# Driver.net
KiCad netlist of a schematic drawn in Altium Designer
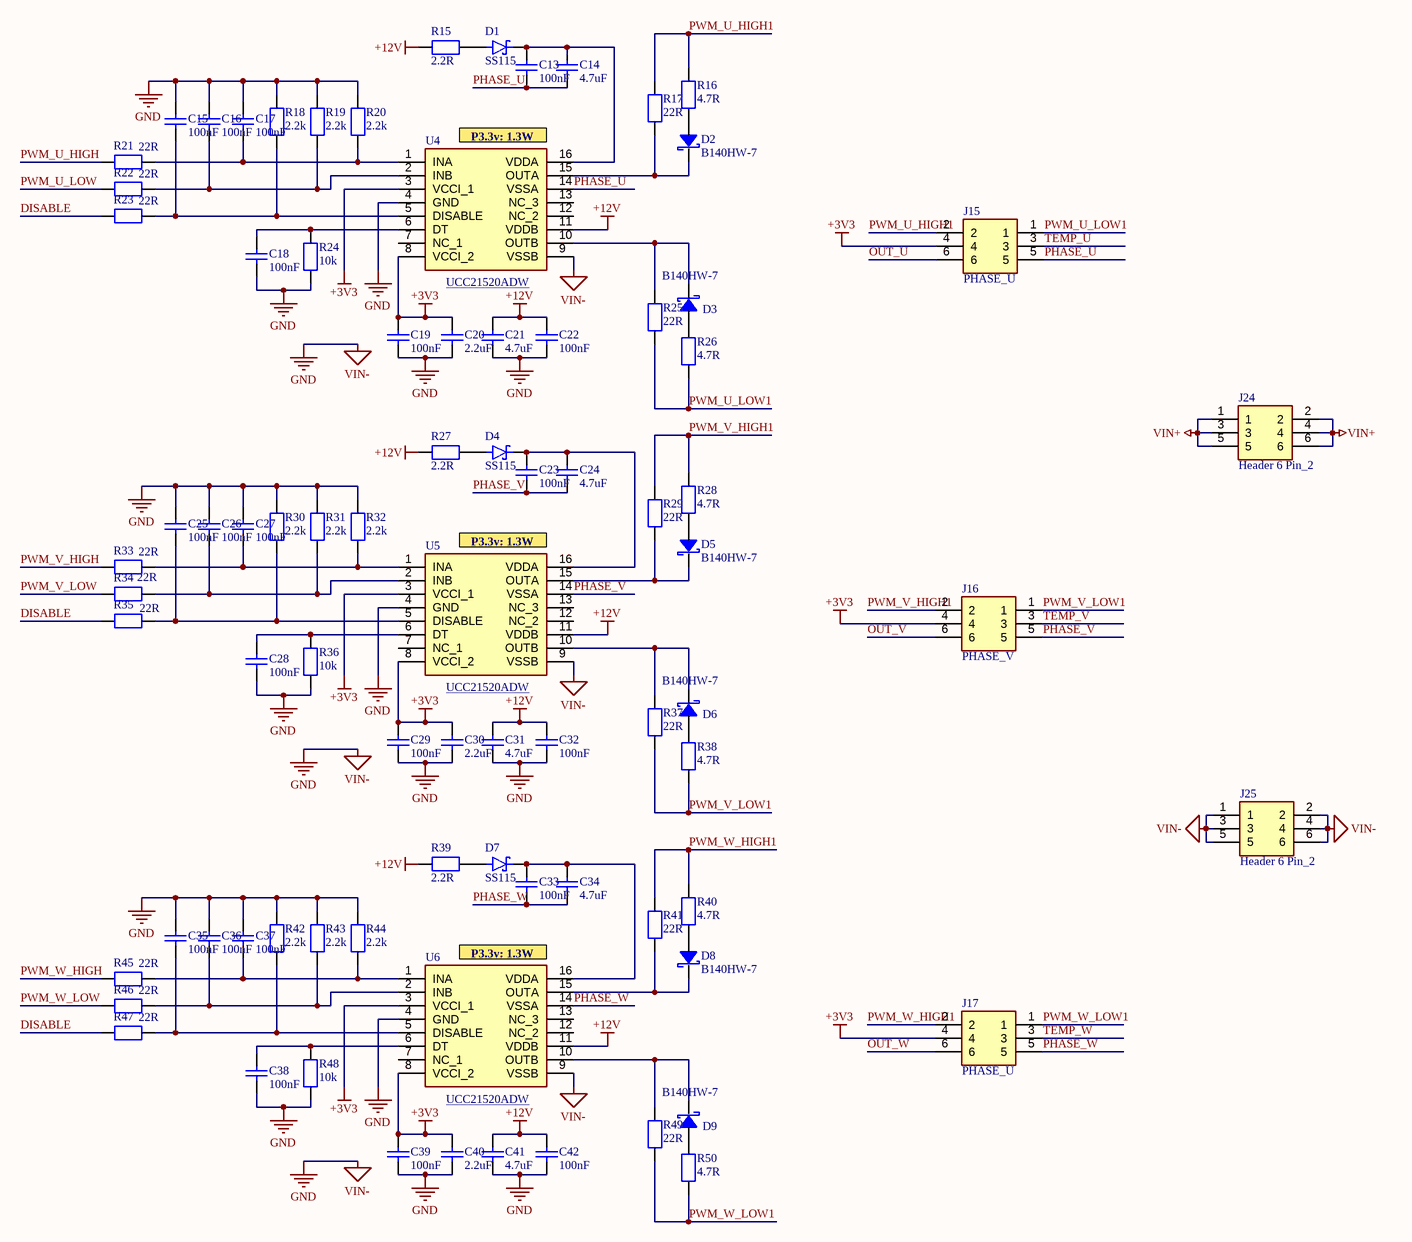
[diagram p0: Driver.SchDoc]

(export (version "E")
  (design (tool "Eeschema 10.0.6"))
  (components
    (comp (ref "C13")
      (value "100nF")
      (footprint "C0603")
      (description "100nF ± 10% 50V")
      (fields
        (field (name "MANUFACTURER") "Yageo")
        (field (name "MANUFACTURER PART NUMBER") "CS0603KRX7R9BB104")
      )
      (libsource (lib "VESC_MotorController") (part "100nF ± 10% 50V"))
    )
    (comp (ref "C14")
      (value "4.7uF")
      (footprint "C0603")
      (description "4.7uF ± 10% 50V")
      (fields
        (field (name "MANUFACTURER") "Yageo")
        (field (name "MANUFACTURER PART NUMBER") "GRM188R61H225ME11J")
      )
      (libsource (lib "VESC_MotorController") (part "4.7uF ± 10% 50V"))
    )
    (comp (ref "C15")
      (value "100nF")
      (footprint "C0603")
      (description "100nF ± 10% 50V")
      (fields
        (field (name "MANUFACTURER") "Yageo")
        (field (name "MANUFACTURER PART NUMBER") "CS0603KRX7R9BB104")
      )
      (libsource (lib "VESC_MotorController") (part "100nF ± 10% 50V"))
    )
    (comp (ref "C16")
      (value "100nF")
      (footprint "C0603")
      (description "100nF ± 10% 50V")
      (fields
        (field (name "MANUFACTURER") "Yageo")
        (field (name "MANUFACTURER PART NUMBER") "CS0603KRX7R9BB104")
      )
      (libsource (lib "VESC_MotorController") (part "100nF ± 10% 50V"))
    )
    (comp (ref "C17")
      (value "100nF")
      (footprint "C0603")
      (description "100nF ± 10% 50V")
      (fields
        (field (name "MANUFACTURER") "Yageo")
        (field (name "MANUFACTURER PART NUMBER") "CS0603KRX7R9BB104")
      )
      (libsource (lib "VESC_MotorController") (part "100nF ± 10% 50V"))
    )
    (comp (ref "C18")
      (value "100nF")
      (footprint "C0603")
      (description "100nF ± 10% 50V")
      (fields
        (field (name "MANUFACTURER") "Yageo")
        (field (name "MANUFACTURER PART NUMBER") "CS0603KRX7R9BB104")
      )
      (libsource (lib "VESC_MotorController") (part "100nF ± 10% 50V"))
    )
    (comp (ref "C19")
      (value "100nF")
      (footprint "C0603")
      (description "100nF ± 10% 50V")
      (fields
        (field (name "MANUFACTURER") "Yageo")
        (field (name "MANUFACTURER PART NUMBER") "CS0603KRX7R9BB104")
      )
      (libsource (lib "VESC_MotorController") (part "100nF ± 10% 50V"))
    )
    (comp (ref "C20")
      (value "2.2uF")
      (footprint "C0603")
      (description "2.2uF ± 10% 50V")
      (fields
        (field (name "MANUFACTURER") "Yageo")
        (field (name "MANUFACTURER PART NUMBER") "GRM188R61H225ME11J")
      )
      (libsource (lib "VESC_MotorController") (part "2.2uF ± 10% 50V"))
    )
    (comp (ref "C21")
      (value "4.7uF")
      (footprint "C0603")
      (description "4.7uF ± 10% 50V")
      (fields
        (field (name "MANUFACTURER") "Yageo")
        (field (name "MANUFACTURER PART NUMBER") "GRM188R61H225ME11J")
      )
      (libsource (lib "VESC_MotorController") (part "4.7uF ± 10% 50V"))
    )
    (comp (ref "C22")
      (value "100nF")
      (footprint "C0603")
      (description "100nF ± 10% 50V")
      (fields
        (field (name "MANUFACTURER") "Yageo")
        (field (name "MANUFACTURER PART NUMBER") "CS0603KRX7R9BB104")
      )
      (libsource (lib "VESC_MotorController") (part "100nF ± 10% 50V"))
    )
    (comp (ref "C23")
      (value "100nF")
      (footprint "C0603")
      (description "100nF ± 10% 50V")
      (fields
        (field (name "MANUFACTURER") "Yageo")
        (field (name "MANUFACTURER PART NUMBER") "CS0603KRX7R9BB104")
      )
      (libsource (lib "VESC_MotorController") (part "100nF ± 10% 50V"))
    )
    (comp (ref "C24")
      (value "4.7uF")
      (footprint "C0603")
      (description "4.7uF ± 10% 50V")
      (fields
        (field (name "MANUFACTURER") "Yageo")
        (field (name "MANUFACTURER PART NUMBER") "GRM188R61H225ME11J")
      )
      (libsource (lib "VESC_MotorController") (part "4.7uF ± 10% 50V"))
    )
    (comp (ref "C25")
      (value "100nF")
      (footprint "C0603")
      (description "100nF ± 10% 50V")
      (fields
        (field (name "MANUFACTURER") "Yageo")
        (field (name "MANUFACTURER PART NUMBER") "CS0603KRX7R9BB104")
      )
      (libsource (lib "VESC_MotorController") (part "100nF ± 10% 50V"))
    )
    (comp (ref "C26")
      (value "100nF")
      (footprint "C0603")
      (description "100nF ± 10% 50V")
      (fields
        (field (name "MANUFACTURER") "Yageo")
        (field (name "MANUFACTURER PART NUMBER") "CS0603KRX7R9BB104")
      )
      (libsource (lib "VESC_MotorController") (part "100nF ± 10% 50V"))
    )
    (comp (ref "C27")
      (value "100nF")
      (footprint "C0603")
      (description "100nF ± 10% 50V")
      (fields
        (field (name "MANUFACTURER") "Yageo")
        (field (name "MANUFACTURER PART NUMBER") "CS0603KRX7R9BB104")
      )
      (libsource (lib "VESC_MotorController") (part "100nF ± 10% 50V"))
    )
    (comp (ref "C28")
      (value "100nF")
      (footprint "C0603")
      (description "100nF ± 10% 50V")
      (fields
        (field (name "MANUFACTURER") "Yageo")
        (field (name "MANUFACTURER PART NUMBER") "CS0603KRX7R9BB104")
      )
      (libsource (lib "VESC_MotorController") (part "100nF ± 10% 50V"))
    )
    (comp (ref "C29")
      (value "100nF")
      (footprint "C0603")
      (description "100nF ± 10% 50V")
      (fields
        (field (name "MANUFACTURER") "Yageo")
        (field (name "MANUFACTURER PART NUMBER") "CS0603KRX7R9BB104")
      )
      (libsource (lib "VESC_MotorController") (part "100nF ± 10% 50V"))
    )
    (comp (ref "C30")
      (value "2.2uF")
      (footprint "C0603")
      (description "2.2uF ± 10% 50V")
      (fields
        (field (name "MANUFACTURER") "Yageo")
        (field (name "MANUFACTURER PART NUMBER") "GRM188R61H225ME11J")
      )
      (libsource (lib "VESC_MotorController") (part "2.2uF ± 10% 50V"))
    )
    (comp (ref "C31")
      (value "4.7uF")
      (footprint "C0603")
      (description "4.7uF ± 10% 50V")
      (fields
        (field (name "MANUFACTURER") "Yageo")
        (field (name "MANUFACTURER PART NUMBER") "GRM188R61H225ME11J")
      )
      (libsource (lib "VESC_MotorController") (part "4.7uF ± 10% 50V"))
    )
    (comp (ref "C32")
      (value "100nF")
      (footprint "C0603")
      (description "100nF ± 10% 50V")
      (fields
        (field (name "MANUFACTURER") "Yageo")
        (field (name "MANUFACTURER PART NUMBER") "CS0603KRX7R9BB104")
      )
      (libsource (lib "VESC_MotorController") (part "100nF ± 10% 50V"))
    )
    (comp (ref "C33")
      (value "100nF")
      (footprint "C0603")
      (description "100nF ± 10% 50V")
      (fields
        (field (name "MANUFACTURER") "Yageo")
        (field (name "MANUFACTURER PART NUMBER") "CS0603KRX7R9BB104")
      )
      (libsource (lib "VESC_MotorController") (part "100nF ± 10% 50V"))
    )
    (comp (ref "C34")
      (value "4.7uF")
      (footprint "C0603")
      (description "4.7uF ± 10% 50V")
      (fields
        (field (name "MANUFACTURER") "Yageo")
        (field (name "MANUFACTURER PART NUMBER") "GRM188R61H225ME11J")
      )
      (libsource (lib "VESC_MotorController") (part "4.7uF ± 10% 50V"))
    )
    (comp (ref "C35")
      (value "100nF")
      (footprint "C0603")
      (description "100nF ± 10% 50V")
      (fields
        (field (name "MANUFACTURER") "Yageo")
        (field (name "MANUFACTURER PART NUMBER") "CS0603KRX7R9BB104")
      )
      (libsource (lib "VESC_MotorController") (part "100nF ± 10% 50V"))
    )
    (comp (ref "C36")
      (value "100nF")
      (footprint "C0603")
      (description "100nF ± 10% 50V")
      (fields
        (field (name "MANUFACTURER") "Yageo")
        (field (name "MANUFACTURER PART NUMBER") "CS0603KRX7R9BB104")
      )
      (libsource (lib "VESC_MotorController") (part "100nF ± 10% 50V"))
    )
    (comp (ref "C37")
      (value "100nF")
      (footprint "C0603")
      (description "100nF ± 10% 50V")
      (fields
        (field (name "MANUFACTURER") "Yageo")
        (field (name "MANUFACTURER PART NUMBER") "CS0603KRX7R9BB104")
      )
      (libsource (lib "VESC_MotorController") (part "100nF ± 10% 50V"))
    )
    (comp (ref "C38")
      (value "100nF")
      (footprint "C0603")
      (description "100nF ± 10% 50V")
      (fields
        (field (name "MANUFACTURER") "Yageo")
        (field (name "MANUFACTURER PART NUMBER") "CS0603KRX7R9BB104")
      )
      (libsource (lib "VESC_MotorController") (part "100nF ± 10% 50V"))
    )
    (comp (ref "C39")
      (value "100nF")
      (footprint "C0603")
      (description "100nF ± 10% 50V")
      (fields
        (field (name "MANUFACTURER") "Yageo")
        (field (name "MANUFACTURER PART NUMBER") "CS0603KRX7R9BB104")
      )
      (libsource (lib "VESC_MotorController") (part "100nF ± 10% 50V"))
    )
    (comp (ref "C40")
      (value "2.2uF")
      (footprint "C0603")
      (description "2.2uF ± 10% 50V")
      (fields
        (field (name "MANUFACTURER") "Yageo")
        (field (name "MANUFACTURER PART NUMBER") "GRM188R61H225ME11J")
      )
      (libsource (lib "VESC_MotorController") (part "2.2uF ± 10% 50V"))
    )
    (comp (ref "C41")
      (value "4.7uF")
      (footprint "C0603")
      (description "4.7uF ± 10% 50V")
      (fields
        (field (name "MANUFACTURER") "Yageo")
        (field (name "MANUFACTURER PART NUMBER") "GRM188R61H225ME11J")
      )
      (libsource (lib "VESC_MotorController") (part "4.7uF ± 10% 50V"))
    )
    (comp (ref "C42")
      (value "100nF")
      (footprint "C0603")
      (description "100nF ± 10% 50V")
      (fields
        (field (name "MANUFACTURER") "Yageo")
        (field (name "MANUFACTURER PART NUMBER") "CS0603KRX7R9BB104")
      )
      (libsource (lib "VESC_MotorController") (part "100nF ± 10% 50V"))
    )
    (comp (ref "D1")
      (value "SS115")
      (footprint "DIOM4325X250N")
      (description "Schottky Diodes & Rectifiers 1A, 150V, Schottky Rectifier")
      (fields (field (name "MANUFACTURER") "Taiwan Semiconductor"))
      (libsource (lib "VESC_MotorController") (part "SS115"))
    )
    (comp (ref "D2")
      (value "B140HW-7")
      (footprint "SOD123")
      (description "Schottky Diodes & Rectifiers 1A, 40V")
      (fields (field (name "MANUFACTURER") "Diodes"))
      (libsource (lib "VESC_MotorController") (part "B140HW-7"))
    )
    (comp (ref "D3")
      (value "B140HW-7")
      (footprint "SOD123")
      (description "Schottky Diodes & Rectifiers 1A, 40V")
      (fields (field (name "MANUFACTURER") "Diodes"))
      (libsource (lib "VESC_MotorController") (part "B140HW-7"))
    )
    (comp (ref "D4")
      (value "SS115")
      (footprint "DIOM4325X250N")
      (description "Schottky Diodes & Rectifiers 1A, 150V, Schottky Rectifier")
      (fields (field (name "MANUFACTURER") "Taiwan Semiconductor"))
      (libsource (lib "VESC_MotorController") (part "SS115"))
    )
    (comp (ref "D5")
      (value "B140HW-7")
      (footprint "SOD123")
      (description "Schottky Diodes & Rectifiers 1A, 40V")
      (fields (field (name "MANUFACTURER") "Diodes"))
      (libsource (lib "VESC_MotorController") (part "B140HW-7"))
    )
    (comp (ref "D6")
      (value "B140HW-7")
      (footprint "SOD123")
      (description "Schottky Diodes & Rectifiers 1A, 40V")
      (fields (field (name "MANUFACTURER") "Diodes"))
      (libsource (lib "VESC_MotorController") (part "B140HW-7"))
    )
    (comp (ref "D7")
      (value "SS115")
      (footprint "DIOM4325X250N")
      (description "Schottky Diodes & Rectifiers 1A, 150V, Schottky Rectifier")
      (fields (field (name "MANUFACTURER") "Taiwan Semiconductor"))
      (libsource (lib "VESC_MotorController") (part "SS115"))
    )
    (comp (ref "D8")
      (value "B140HW-7")
      (footprint "SOD123")
      (description "Schottky Diodes & Rectifiers 1A, 40V")
      (fields (field (name "MANUFACTURER") "Diodes"))
      (libsource (lib "VESC_MotorController") (part "B140HW-7"))
    )
    (comp (ref "D9")
      (value "B140HW-7")
      (footprint "SOD123")
      (description "Schottky Diodes & Rectifiers 1A, 40V")
      (fields (field (name "MANUFACTURER") "Diodes"))
      (libsource (lib "VESC_MotorController") (part "B140HW-7"))
    )
    (comp (ref "J15")
      (value "PHASE_U")
      (footprint "61300621121")
      (fields
        (field (name "MANUFACTURER") "Wurth Elektronik")
        (field (name "MANUFACTURER PART NUMBER") "61300621121")
      )
      (libsource (lib "") (part "Header 6 Pin_2_1"))
    )
    (comp (ref "J16")
      (value "PHASE_V")
      (footprint "61300621121")
      (fields
        (field (name "MANUFACTURER") "Wurth Elektronik")
        (field (name "MANUFACTURER PART NUMBER") "61300621121")
      )
      (libsource (lib "") (part "Header 6 Pin_2_1"))
    )
    (comp (ref "J17")
      (value "PHASE_U")
      (footprint "61300621121")
      (fields
        (field (name "MANUFACTURER") "Wurth Elektronik")
        (field (name "MANUFACTURER PART NUMBER") "61300621121")
      )
      (libsource (lib "") (part "Header 6 Pin_2_1"))
    )
    (comp (ref "J24")
      (value "Header 6 Pin_2")
      (footprint "61300621121")
      (fields
        (field (name "MANUFACTURER") "Wurth Elektronik")
        (field (name "MANUFACTURER PART NUMBER") "61300621121")
      )
      (libsource (lib "VESC_MotorController") (part "Header 6 Pin_2"))
    )
    (comp (ref "J25")
      (value "Header 6 Pin_2")
      (footprint "61300621121")
      (fields
        (field (name "MANUFACTURER") "Wurth Elektronik")
        (field (name "MANUFACTURER PART NUMBER") "61300621121")
      )
      (libsource (lib "VESC_MotorController") (part "Header 6 Pin_2"))
    )
    (comp (ref "R15")
      (value "2.2R")
      (footprint "R0603")
      (description "2.2 ohm 0.1W ±1%")
      (fields
        (field (name "MANUFACTURER PART NUMBER") "RC0603FR-072R2L")
        (field (name "MANUFACTURER") "Yageo")
      )
      (libsource (lib "VESC_MotorController") (part "2.2ohm 0.1W ±1%"))
    )
    (comp (ref "R16")
      (value "4.7R")
      (footprint "R0603")
      (description "4.7 ohm 0.1W ±1%")
      (fields
        (field (name "MANUFACTURER PART NUMBER") "RC1206FR-074R7L")
        (field (name "MANUFACTURER") "Yageo")
      )
      (libsource (lib "VESC_MotorController") (part "4.7ohm 0.1W ±10%"))
    )
    (comp (ref "R17")
      (value "22R")
      (footprint "R0603")
      (description "22 ohm 0.1W ±1%")
      (fields
        (field (name "MANUFACTURER PART NUMBER") "RC0603FR-0722RL")
        (field (name "MANUFACTURER") "Yageo")
      )
      (libsource (lib "VESC_MotorController") (part "22ohm 0.1W ±1%"))
    )
    (comp (ref "R18")
      (value "2.2k")
      (footprint "R0603")
      (description "2.2 kOhms ±1% 0.1W")
      (fields
        (field (name "MANUFACTURER") "Yageo")
        (field (name "MANUFACTURER PART NUMBER") "RC0603FR-072K2L")
      )
      (libsource (lib "VESC_MotorController") (part "2.2 kOhms ±1% 0.1W"))
    )
    (comp (ref "R19")
      (value "2.2k")
      (footprint "R0603")
      (description "2.2 kOhms ±1% 0.1W")
      (fields
        (field (name "MANUFACTURER") "Yageo")
        (field (name "MANUFACTURER PART NUMBER") "RC0603FR-072K2L")
      )
      (libsource (lib "VESC_MotorController") (part "2.2 kOhms ±1% 0.1W"))
    )
    (comp (ref "R20")
      (value "2.2k")
      (footprint "R0603")
      (description "2.2 kOhms ±1% 0.1W")
      (fields
        (field (name "MANUFACTURER") "Yageo")
        (field (name "MANUFACTURER PART NUMBER") "RC0603FR-072K2L")
      )
      (libsource (lib "VESC_MotorController") (part "2.2 kOhms ±1% 0.1W"))
    )
    (comp (ref "R21")
      (value "22R")
      (footprint "R0603")
      (description "22 ohm 0.1W ±1%")
      (fields
        (field (name "MANUFACTURER PART NUMBER") "RC0603FR-0722RL")
        (field (name "MANUFACTURER") "Yageo")
      )
      (libsource (lib "VESC_MotorController") (part "22ohm 0.1W ±1%"))
    )
    (comp (ref "R22")
      (value "22R")
      (footprint "R0603")
      (description "22 ohm 0.1W ±1%")
      (fields
        (field (name "MANUFACTURER PART NUMBER") "RC0603FR-0722RL")
        (field (name "MANUFACTURER") "Yageo")
      )
      (libsource (lib "VESC_MotorController") (part "22ohm 0.1W ±1%"))
    )
    (comp (ref "R23")
      (value "22R")
      (footprint "R0603")
      (description "22 ohm 0.1W ±1%")
      (fields
        (field (name "MANUFACTURER PART NUMBER") "RC0603FR-0722RL")
        (field (name "MANUFACTURER") "Yageo")
      )
      (libsource (lib "VESC_MotorController") (part "22ohm 0.1W ±1%"))
    )
    (comp (ref "R24")
      (value "10k")
      (footprint "R0603")
      (description "10 kOhms ±1% 0.1W")
      (fields
        (field (name "MANUFACTURER") "Yageo")
        (field (name "MANUFACTURER PART NUMBER") "RC0603FR-0710KL")
      )
      (libsource (lib "VESC_MotorController") (part "10 kOhms ±1% 0.1W"))
    )
    (comp (ref "R25")
      (value "22R")
      (footprint "R0603")
      (description "22 ohm 0.1W ±1%")
      (fields
        (field (name "MANUFACTURER PART NUMBER") "RC0603FR-0722RL")
        (field (name "MANUFACTURER") "Yageo")
      )
      (libsource (lib "VESC_MotorController") (part "22ohm 0.1W ±1%"))
    )
    (comp (ref "R26")
      (value "4.7R")
      (footprint "R0603")
      (description "4.7 ohm 0.1W ±1%")
      (fields
        (field (name "MANUFACTURER PART NUMBER") "RC1206FR-074R7L")
        (field (name "MANUFACTURER") "Yageo")
      )
      (libsource (lib "VESC_MotorController") (part "4.7ohm 0.1W ±10%"))
    )
    (comp (ref "R27")
      (value "2.2R")
      (footprint "R0603")
      (description "2.2 ohm 0.1W ±1%")
      (fields
        (field (name "MANUFACTURER PART NUMBER") "RC0603FR-072R2L")
        (field (name "MANUFACTURER") "Yageo")
      )
      (libsource (lib "VESC_MotorController") (part "2.2ohm 0.1W ±1%"))
    )
    (comp (ref "R28")
      (value "4.7R")
      (footprint "R0603")
      (description "4.7 ohm 0.1W ±1%")
      (fields
        (field (name "MANUFACTURER PART NUMBER") "RC1206FR-074R7L")
        (field (name "MANUFACTURER") "Yageo")
      )
      (libsource (lib "VESC_MotorController") (part "4.7ohm 0.1W ±10%"))
    )
    (comp (ref "R29")
      (value "22R")
      (footprint "R0603")
      (description "22 ohm 0.1W ±1%")
      (fields
        (field (name "MANUFACTURER PART NUMBER") "RC0603FR-0722RL")
        (field (name "MANUFACTURER") "Yageo")
      )
      (libsource (lib "VESC_MotorController") (part "22ohm 0.1W ±1%"))
    )
    (comp (ref "R30")
      (value "2.2k")
      (footprint "R0603")
      (description "2.2 kOhms ±1% 0.1W")
      (fields
        (field (name "MANUFACTURER") "Yageo")
        (field (name "MANUFACTURER PART NUMBER") "RC0603FR-072K2L")
      )
      (libsource (lib "VESC_MotorController") (part "2.2 kOhms ±1% 0.1W"))
    )
    (comp (ref "R31")
      (value "2.2k")
      (footprint "R0603")
      (description "2.2 kOhms ±1% 0.1W")
      (fields
        (field (name "MANUFACTURER") "Yageo")
        (field (name "MANUFACTURER PART NUMBER") "RC0603FR-072K2L")
      )
      (libsource (lib "VESC_MotorController") (part "2.2 kOhms ±1% 0.1W"))
    )
    (comp (ref "R32")
      (value "2.2k")
      (footprint "R0603")
      (description "2.2 kOhms ±1% 0.1W")
      (fields
        (field (name "MANUFACTURER") "Yageo")
        (field (name "MANUFACTURER PART NUMBER") "RC0603FR-072K2L")
      )
      (libsource (lib "VESC_MotorController") (part "2.2 kOhms ±1% 0.1W"))
    )
    (comp (ref "R33")
      (value "22R")
      (footprint "R0603")
      (description "22 ohm 0.1W ±1%")
      (fields
        (field (name "MANUFACTURER PART NUMBER") "RC0603FR-0722RL")
        (field (name "MANUFACTURER") "Yageo")
      )
      (libsource (lib "VESC_MotorController") (part "22ohm 0.1W ±1%"))
    )
    (comp (ref "R34")
      (value "22R")
      (footprint "R0603")
      (description "22 ohm 0.1W ±1%")
      (fields
        (field (name "MANUFACTURER PART NUMBER") "RC0603FR-0722RL")
        (field (name "MANUFACTURER") "Yageo")
      )
      (libsource (lib "VESC_MotorController") (part "22ohm 0.1W ±1%"))
    )
    (comp (ref "R35")
      (value "22R")
      (footprint "R0603")
      (description "22 ohm 0.1W ±1%")
      (fields
        (field (name "MANUFACTURER PART NUMBER") "RC0603FR-0722RL")
        (field (name "MANUFACTURER") "Yageo")
      )
      (libsource (lib "VESC_MotorController") (part "22ohm 0.1W ±1%"))
    )
    (comp (ref "R36")
      (value "10k")
      (footprint "R0603")
      (description "10 kOhms ±1% 0.1W")
      (fields
        (field (name "MANUFACTURER") "Yageo")
        (field (name "MANUFACTURER PART NUMBER") "RC0603FR-0710KL")
      )
      (libsource (lib "VESC_MotorController") (part "10 kOhms ±1% 0.1W"))
    )
    (comp (ref "R37")
      (value "22R")
      (footprint "R0603")
      (description "22 ohm 0.1W ±1%")
      (fields
        (field (name "MANUFACTURER PART NUMBER") "RC0603FR-0722RL")
        (field (name "MANUFACTURER") "Yageo")
      )
      (libsource (lib "VESC_MotorController") (part "22ohm 0.1W ±1%"))
    )
    (comp (ref "R38")
      (value "4.7R")
      (footprint "R0603")
      (description "4.7 ohm 0.1W ±1%")
      (fields
        (field (name "MANUFACTURER PART NUMBER") "RC1206FR-074R7L")
        (field (name "MANUFACTURER") "Yageo")
      )
      (libsource (lib "VESC_MotorController") (part "4.7ohm 0.1W ±10%"))
    )
    (comp (ref "R39")
      (value "2.2R")
      (footprint "R0603")
      (description "2.2 ohm 0.1W ±1%")
      (fields
        (field (name "MANUFACTURER PART NUMBER") "RC0603FR-072R2L")
        (field (name "MANUFACTURER") "Yageo")
      )
      (libsource (lib "VESC_MotorController") (part "2.2ohm 0.1W ±1%"))
    )
    (comp (ref "R40")
      (value "4.7R")
      (footprint "R0603")
      (description "4.7 ohm 0.1W ±1%")
      (fields
        (field (name "MANUFACTURER PART NUMBER") "RC1206FR-074R7L")
        (field (name "MANUFACTURER") "Yageo")
      )
      (libsource (lib "VESC_MotorController") (part "4.7ohm 0.1W ±10%"))
    )
    (comp (ref "R41")
      (value "22R")
      (footprint "R0603")
      (description "22 ohm 0.1W ±1%")
      (fields
        (field (name "MANUFACTURER PART NUMBER") "RC0603FR-0722RL")
        (field (name "MANUFACTURER") "Yageo")
      )
      (libsource (lib "VESC_MotorController") (part "22ohm 0.1W ±1%"))
    )
    (comp (ref "R42")
      (value "2.2k")
      (footprint "R0603")
      (description "2.2 kOhms ±1% 0.1W")
      (fields
        (field (name "MANUFACTURER") "Yageo")
        (field (name "MANUFACTURER PART NUMBER") "RC0603FR-072K2L")
      )
      (libsource (lib "VESC_MotorController") (part "2.2 kOhms ±1% 0.1W"))
    )
    (comp (ref "R43")
      (value "2.2k")
      (footprint "R0603")
      (description "2.2 kOhms ±1% 0.1W")
      (fields
        (field (name "MANUFACTURER") "Yageo")
        (field (name "MANUFACTURER PART NUMBER") "RC0603FR-072K2L")
      )
      (libsource (lib "VESC_MotorController") (part "2.2 kOhms ±1% 0.1W"))
    )
    (comp (ref "R44")
      (value "2.2k")
      (footprint "R0603")
      (description "2.2 kOhms ±1% 0.1W")
      (fields
        (field (name "MANUFACTURER") "Yageo")
        (field (name "MANUFACTURER PART NUMBER") "RC0603FR-072K2L")
      )
      (libsource (lib "VESC_MotorController") (part "2.2 kOhms ±1% 0.1W"))
    )
    (comp (ref "R45")
      (value "22R")
      (footprint "R0603")
      (description "22 ohm 0.1W ±1%")
      (fields
        (field (name "MANUFACTURER PART NUMBER") "RC0603FR-0722RL")
        (field (name "MANUFACTURER") "Yageo")
      )
      (libsource (lib "VESC_MotorController") (part "22ohm 0.1W ±1%"))
    )
    (comp (ref "R46")
      (value "22R")
      (footprint "R0603")
      (description "22 ohm 0.1W ±1%")
      (fields
        (field (name "MANUFACTURER PART NUMBER") "RC0603FR-0722RL")
        (field (name "MANUFACTURER") "Yageo")
      )
      (libsource (lib "VESC_MotorController") (part "22ohm 0.1W ±1%"))
    )
    (comp (ref "R47")
      (value "22R")
      (footprint "R0603")
      (description "22 ohm 0.1W ±1%")
      (fields
        (field (name "MANUFACTURER PART NUMBER") "RC0603FR-0722RL")
        (field (name "MANUFACTURER") "Yageo")
      )
      (libsource (lib "VESC_MotorController") (part "22ohm 0.1W ±1%"))
    )
    (comp (ref "R48")
      (value "10k")
      (footprint "R0603")
      (description "10 kOhms ±1% 0.1W")
      (fields
        (field (name "MANUFACTURER") "Yageo")
        (field (name "MANUFACTURER PART NUMBER") "RC0603FR-0710KL")
      )
      (libsource (lib "VESC_MotorController") (part "10 kOhms ±1% 0.1W"))
    )
    (comp (ref "R49")
      (value "22R")
      (footprint "R0603")
      (description "22 ohm 0.1W ±1%")
      (fields
        (field (name "MANUFACTURER PART NUMBER") "RC0603FR-0722RL")
        (field (name "MANUFACTURER") "Yageo")
      )
      (libsource (lib "VESC_MotorController") (part "22ohm 0.1W ±1%"))
    )
    (comp (ref "R50")
      (value "4.7R")
      (footprint "R0603")
      (description "4.7 ohm 0.1W ±1%")
      (fields
        (field (name "MANUFACTURER PART NUMBER") "RC1206FR-074R7L")
        (field (name "MANUFACTURER") "Yageo")
      )
      (libsource (lib "VESC_MotorController") (part "4.7ohm 0.1W ±10%"))
    )
    (comp (ref "U4")
      (value "UCC21520ADW")
      (footprint "SOIC127P1030X265-16N")
      (description "4A/6A, 5.7 kVrms Isolated Dual Channel Gate Driver")
      (fields (field (name "MANUFACTURER") "Texas Instruments"))
      (libsource (lib "VESC_MotorController") (part "UCC21520ADW"))
    )
    (comp (ref "U5")
      (value "UCC21520ADW")
      (footprint "SOIC127P1030X265-16N")
      (description "4A/6A, 5.7 kVrms Isolated Dual Channel Gate Driver")
      (fields (field (name "MANUFACTURER") "Texas Instruments"))
      (libsource (lib "VESC_MotorController") (part "UCC21520ADW"))
    )
    (comp (ref "U6")
      (value "UCC21520ADW")
      (footprint "SOIC127P1030X265-16N")
      (description "4A/6A, 5.7 kVrms Isolated Dual Channel Gate Driver")
      (fields (field (name "MANUFACTURER") "Texas Instruments"))
      (libsource (lib "VESC_MotorController") (part "UCC21520ADW"))
    )
  )
  (nets
    (net (code "1") (name "+3V3") (class "Default")
      (node (ref "C19") (pin "2") (pinfunction "2_2") (pintype "passive"))
      (node (ref "C20") (pin "2") (pinfunction "2_2") (pintype "passive"))
      (node (ref "C29") (pin "2") (pinfunction "2_2") (pintype "passive"))
      (node (ref "C30") (pin "2") (pinfunction "2_2") (pintype "passive"))
      (node (ref "C39") (pin "2") (pinfunction "2_2") (pintype "passive"))
      (node (ref "C40") (pin "2") (pinfunction "2_2") (pintype "passive"))
      (node (ref "J15") (pin "4") (pinfunction "4_4") (pintype "passive"))
      (node (ref "J16") (pin "4") (pinfunction "4_4") (pintype "passive"))
      (node (ref "J17") (pin "4") (pinfunction "4_4") (pintype "passive"))
      (node (ref "U4") (pin "3") (pinfunction "VCCI_1_3") (pintype "passive"))
      (node (ref "U4") (pin "8") (pinfunction "VCCI_2_8") (pintype "passive"))
      (node (ref "U5") (pin "3") (pinfunction "VCCI_1_3") (pintype "passive"))
      (node (ref "U5") (pin "8") (pinfunction "VCCI_2_8") (pintype "passive"))
      (node (ref "U6") (pin "3") (pinfunction "VCCI_1_3") (pintype "passive"))
      (node (ref "U6") (pin "8") (pinfunction "VCCI_2_8") (pintype "passive"))
    )
    (net (code "2") (name "+12V") (class "Default")
      (node (ref "C21") (pin "2") (pinfunction "2_2") (pintype "passive"))
      (node (ref "C22") (pin "2") (pinfunction "2_2") (pintype "passive"))
      (node (ref "C31") (pin "2") (pinfunction "2_2") (pintype "passive"))
      (node (ref "C32") (pin "2") (pinfunction "2_2") (pintype "passive"))
      (node (ref "C41") (pin "2") (pinfunction "2_2") (pintype "passive"))
      (node (ref "C42") (pin "2") (pinfunction "2_2") (pintype "passive"))
      (node (ref "R15") (pin "1") (pinfunction "1_1") (pintype "passive"))
      (node (ref "R27") (pin "1") (pinfunction "1_1") (pintype "passive"))
      (node (ref "R39") (pin "1") (pinfunction "1_1") (pintype "passive"))
      (node (ref "U4") (pin "11") (pinfunction "VDDB_11") (pintype "passive"))
      (node (ref "U5") (pin "11") (pinfunction "VDDB_11") (pintype "passive"))
      (node (ref "U6") (pin "11") (pinfunction "VDDB_11") (pintype "passive"))
    )
    (net (code "3") (name "/DISABLE") (class "Default")
      (node (ref "R23") (pin "1") (pinfunction "1_1") (pintype "passive"))
      (node (ref "R35") (pin "1") (pinfunction "1_1") (pintype "passive"))
      (node (ref "R47") (pin "1") (pinfunction "1_1") (pintype "passive"))
    )
    (net (code "4") (name "/OUT_U") (class "Default")
      (node (ref "J15") (pin "6") (pinfunction "6_6") (pintype "passive"))
    )
    (net (code "5") (name "/OUT_V") (class "Default")
      (node (ref "J16") (pin "6") (pinfunction "6_6") (pintype "passive"))
    )
    (net (code "6") (name "/OUT_W") (class "Default")
      (node (ref "J17") (pin "6") (pinfunction "6_6") (pintype "passive"))
    )
    (net (code "7") (name "/PHASE_U") (class "Default")
      (node (ref "C13") (pin "1") (pinfunction "1_1") (pintype "passive"))
      (node (ref "C14") (pin "1") (pinfunction "1_1") (pintype "passive"))
      (node (ref "J15") (pin "5") (pinfunction "5_5") (pintype "passive"))
      (node (ref "U4") (pin "14") (pinfunction "VSSA_14") (pintype "passive"))
    )
    (net (code "8") (name "/PHASE_V") (class "Default")
      (node (ref "C23") (pin "1") (pinfunction "1_1") (pintype "passive"))
      (node (ref "C24") (pin "1") (pinfunction "1_1") (pintype "passive"))
      (node (ref "J16") (pin "5") (pinfunction "5_5") (pintype "passive"))
      (node (ref "U5") (pin "14") (pinfunction "VSSA_14") (pintype "passive"))
    )
    (net (code "9") (name "/PHASE_W") (class "Default")
      (node (ref "C33") (pin "1") (pinfunction "1_1") (pintype "passive"))
      (node (ref "C34") (pin "1") (pinfunction "1_1") (pintype "passive"))
      (node (ref "J17") (pin "5") (pinfunction "5_5") (pintype "passive"))
      (node (ref "U6") (pin "14") (pinfunction "VSSA_14") (pintype "passive"))
    )
    (net (code "10") (name "/PWM_U_HIGH") (class "Default")
      (node (ref "R21") (pin "1") (pinfunction "1_1") (pintype "passive"))
    )
    (net (code "11") (name "/PWM_U_HIGH1") (class "Default")
      (node (ref "J15") (pin "2") (pinfunction "2_2") (pintype "passive"))
      (node (ref "R16") (pin "2") (pinfunction "2_2") (pintype "passive"))
      (node (ref "R17") (pin "2") (pinfunction "2_2") (pintype "passive"))
    )
    (net (code "12") (name "/PWM_U_LOW") (class "Default")
      (node (ref "R22") (pin "1") (pinfunction "1_1") (pintype "passive"))
    )
    (net (code "13") (name "/PWM_U_LOW1") (class "Default")
      (node (ref "J15") (pin "1") (pinfunction "1_1") (pintype "passive"))
      (node (ref "R25") (pin "1") (pinfunction "1_1") (pintype "passive"))
      (node (ref "R26") (pin "1") (pinfunction "1_1") (pintype "passive"))
    )
    (net (code "14") (name "/PWM_V_HIGH") (class "Default")
      (node (ref "R33") (pin "1") (pinfunction "1_1") (pintype "passive"))
    )
    (net (code "15") (name "/PWM_V_HIGH1") (class "Default")
      (node (ref "J16") (pin "2") (pinfunction "2_2") (pintype "passive"))
      (node (ref "R28") (pin "2") (pinfunction "2_2") (pintype "passive"))
      (node (ref "R29") (pin "2") (pinfunction "2_2") (pintype "passive"))
    )
    (net (code "16") (name "/PWM_V_LOW") (class "Default")
      (node (ref "R34") (pin "1") (pinfunction "1_1") (pintype "passive"))
    )
    (net (code "17") (name "/PWM_V_LOW1") (class "Default")
      (node (ref "J16") (pin "1") (pinfunction "1_1") (pintype "passive"))
      (node (ref "R37") (pin "1") (pinfunction "1_1") (pintype "passive"))
      (node (ref "R38") (pin "1") (pinfunction "1_1") (pintype "passive"))
    )
    (net (code "18") (name "/PWM_W_HIGH") (class "Default")
      (node (ref "R45") (pin "1") (pinfunction "1_1") (pintype "passive"))
    )
    (net (code "19") (name "/PWM_W_HIGH1") (class "Default")
      (node (ref "J17") (pin "2") (pinfunction "2_2") (pintype "passive"))
      (node (ref "R40") (pin "2") (pinfunction "2_2") (pintype "passive"))
      (node (ref "R41") (pin "2") (pinfunction "2_2") (pintype "passive"))
    )
    (net (code "20") (name "/PWM_W_LOW") (class "Default")
      (node (ref "R46") (pin "1") (pinfunction "1_1") (pintype "passive"))
    )
    (net (code "21") (name "/PWM_W_LOW1") (class "Default")
      (node (ref "J17") (pin "1") (pinfunction "1_1") (pintype "passive"))
      (node (ref "R49") (pin "1") (pinfunction "1_1") (pintype "passive"))
      (node (ref "R50") (pin "1") (pinfunction "1_1") (pintype "passive"))
    )
    (net (code "22") (name "/TEMP_U") (class "Default")
      (node (ref "J15") (pin "3") (pinfunction "3_3") (pintype "passive"))
    )
    (net (code "23") (name "/TEMP_V") (class "Default")
      (node (ref "J16") (pin "3") (pinfunction "3_3") (pintype "passive"))
    )
    (net (code "24") (name "/TEMP_W") (class "Default")
      (node (ref "J17") (pin "3") (pinfunction "3_3") (pintype "passive"))
    )
    (net (code "25") (name "GND") (class "Default")
      (node (ref "C15") (pin "2") (pinfunction "2_2") (pintype "passive"))
      (node (ref "C16") (pin "2") (pinfunction "2_2") (pintype "passive"))
      (node (ref "C17") (pin "2") (pinfunction "2_2") (pintype "passive"))
      (node (ref "C18") (pin "1") (pinfunction "1_1") (pintype "passive"))
      (node (ref "C19") (pin "1") (pinfunction "1_1") (pintype "passive"))
      (node (ref "C20") (pin "1") (pinfunction "1_1") (pintype "passive"))
      (node (ref "C21") (pin "1") (pinfunction "1_1") (pintype "passive"))
      (node (ref "C22") (pin "1") (pinfunction "1_1") (pintype "passive"))
      (node (ref "C25") (pin "2") (pinfunction "2_2") (pintype "passive"))
      (node (ref "C26") (pin "2") (pinfunction "2_2") (pintype "passive"))
      (node (ref "C27") (pin "2") (pinfunction "2_2") (pintype "passive"))
      (node (ref "C28") (pin "1") (pinfunction "1_1") (pintype "passive"))
      (node (ref "C29") (pin "1") (pinfunction "1_1") (pintype "passive"))
      (node (ref "C30") (pin "1") (pinfunction "1_1") (pintype "passive"))
      (node (ref "C31") (pin "1") (pinfunction "1_1") (pintype "passive"))
      (node (ref "C32") (pin "1") (pinfunction "1_1") (pintype "passive"))
      (node (ref "C35") (pin "2") (pinfunction "2_2") (pintype "passive"))
      (node (ref "C36") (pin "2") (pinfunction "2_2") (pintype "passive"))
      (node (ref "C37") (pin "2") (pinfunction "2_2") (pintype "passive"))
      (node (ref "C38") (pin "1") (pinfunction "1_1") (pintype "passive"))
      (node (ref "C39") (pin "1") (pinfunction "1_1") (pintype "passive"))
      (node (ref "C40") (pin "1") (pinfunction "1_1") (pintype "passive"))
      (node (ref "C41") (pin "1") (pinfunction "1_1") (pintype "passive"))
      (node (ref "C42") (pin "1") (pinfunction "1_1") (pintype "passive"))
      (node (ref "J25") (pin "1") (pinfunction "1_1") (pintype "passive"))
      (node (ref "J25") (pin "2") (pinfunction "2_2") (pintype "passive"))
      (node (ref "J25") (pin "3") (pinfunction "3_3") (pintype "passive"))
      (node (ref "J25") (pin "4") (pinfunction "4_4") (pintype "passive"))
      (node (ref "J25") (pin "5") (pinfunction "5_5") (pintype "passive"))
      (node (ref "J25") (pin "6") (pinfunction "6_6") (pintype "passive"))
      (node (ref "R18") (pin "2") (pinfunction "2_2") (pintype "passive"))
      (node (ref "R19") (pin "2") (pinfunction "2_2") (pintype "passive"))
      (node (ref "R20") (pin "2") (pinfunction "2_2") (pintype "passive"))
      (node (ref "R24") (pin "1") (pinfunction "1_1") (pintype "passive"))
      (node (ref "R30") (pin "2") (pinfunction "2_2") (pintype "passive"))
      (node (ref "R31") (pin "2") (pinfunction "2_2") (pintype "passive"))
      (node (ref "R32") (pin "2") (pinfunction "2_2") (pintype "passive"))
      (node (ref "R36") (pin "1") (pinfunction "1_1") (pintype "passive"))
      (node (ref "R42") (pin "2") (pinfunction "2_2") (pintype "passive"))
      (node (ref "R43") (pin "2") (pinfunction "2_2") (pintype "passive"))
      (node (ref "R44") (pin "2") (pinfunction "2_2") (pintype "passive"))
      (node (ref "R48") (pin "1") (pinfunction "1_1") (pintype "passive"))
      (node (ref "U4") (pin "4") (pinfunction "GND_4") (pintype "passive"))
      (node (ref "U4") (pin "9") (pinfunction "VSSB_9") (pintype "passive"))
      (node (ref "U5") (pin "4") (pinfunction "GND_4") (pintype "passive"))
      (node (ref "U5") (pin "9") (pinfunction "VSSB_9") (pintype "passive"))
      (node (ref "U6") (pin "4") (pinfunction "GND_4") (pintype "passive"))
      (node (ref "U6") (pin "9") (pinfunction "VSSB_9") (pintype "passive"))
    )
    (net (code "26") (name "Net-(D1-K)") (class "Default")
      (node (ref "C13") (pin "2") (pinfunction "2_2") (pintype "passive"))
      (node (ref "C14") (pin "2") (pinfunction "2_2") (pintype "passive"))
      (node (ref "D1") (pin "C") (pinfunction "K_C") (pintype "passive"))
      (node (ref "U4") (pin "16") (pinfunction "VDDA_16") (pintype "passive"))
    )
    (net (code "27") (name "Net-(D1-PadA)") (class "Default")
      (node (ref "D1") (pin "A") (pinfunction "A_A") (pintype "passive"))
      (node (ref "R15") (pin "2") (pinfunction "2_2") (pintype "passive"))
    )
    (net (code "28") (name "Net-(D2-PadA)") (class "Default")
      (node (ref "D2") (pin "A") (pinfunction "A_A") (pintype "passive"))
      (node (ref "R16") (pin "1") (pinfunction "1_1") (pintype "passive"))
    )
    (net (code "29") (name "Net-(D3-PadA)") (class "Default")
      (node (ref "D3") (pin "A") (pinfunction "A_A") (pintype "passive"))
      (node (ref "R26") (pin "2") (pinfunction "2_2") (pintype "passive"))
    )
    (net (code "30") (name "Net-(D4-K)") (class "Default")
      (node (ref "C23") (pin "2") (pinfunction "2_2") (pintype "passive"))
      (node (ref "C24") (pin "2") (pinfunction "2_2") (pintype "passive"))
      (node (ref "D4") (pin "C") (pinfunction "K_C") (pintype "passive"))
      (node (ref "U5") (pin "16") (pinfunction "VDDA_16") (pintype "passive"))
    )
    (net (code "31") (name "Net-(D4-PadA)") (class "Default")
      (node (ref "D4") (pin "A") (pinfunction "A_A") (pintype "passive"))
      (node (ref "R27") (pin "2") (pinfunction "2_2") (pintype "passive"))
    )
    (net (code "32") (name "Net-(D5-PadA)") (class "Default")
      (node (ref "D5") (pin "A") (pinfunction "A_A") (pintype "passive"))
      (node (ref "R28") (pin "1") (pinfunction "1_1") (pintype "passive"))
    )
    (net (code "33") (name "Net-(D6-PadA)") (class "Default")
      (node (ref "D6") (pin "A") (pinfunction "A_A") (pintype "passive"))
      (node (ref "R38") (pin "2") (pinfunction "2_2") (pintype "passive"))
    )
    (net (code "34") (name "Net-(D7-K)") (class "Default")
      (node (ref "C33") (pin "2") (pinfunction "2_2") (pintype "passive"))
      (node (ref "C34") (pin "2") (pinfunction "2_2") (pintype "passive"))
      (node (ref "D7") (pin "C") (pinfunction "K_C") (pintype "passive"))
      (node (ref "U6") (pin "16") (pinfunction "VDDA_16") (pintype "passive"))
    )
    (net (code "35") (name "Net-(D7-PadA)") (class "Default")
      (node (ref "D7") (pin "A") (pinfunction "A_A") (pintype "passive"))
      (node (ref "R39") (pin "2") (pinfunction "2_2") (pintype "passive"))
    )
    (net (code "36") (name "Net-(D8-PadA)") (class "Default")
      (node (ref "D8") (pin "A") (pinfunction "A_A") (pintype "passive"))
      (node (ref "R40") (pin "1") (pinfunction "1_1") (pintype "passive"))
    )
    (net (code "37") (name "Net-(D9-PadA)") (class "Default")
      (node (ref "D9") (pin "A") (pinfunction "A_A") (pintype "passive"))
      (node (ref "R50") (pin "2") (pinfunction "2_2") (pintype "passive"))
    )
    (net (code "38") (name "Net-(U4-DISABLE)") (class "Default")
      (node (ref "C15") (pin "1") (pinfunction "1_1") (pintype "passive"))
      (node (ref "R18") (pin "1") (pinfunction "1_1") (pintype "passive"))
      (node (ref "R23") (pin "2") (pinfunction "2_2") (pintype "passive"))
      (node (ref "U4") (pin "5") (pinfunction "DISABLE_5") (pintype "passive"))
    )
    (net (code "39") (name "Net-(U4-DT)") (class "Default")
      (node (ref "C18") (pin "2") (pinfunction "2_2") (pintype "passive"))
      (node (ref "R24") (pin "2") (pinfunction "2_2") (pintype "passive"))
      (node (ref "U4") (pin "6") (pinfunction "DT_6") (pintype "passive"))
    )
    (net (code "40") (name "Net-(U4-INA)") (class "Default")
      (node (ref "C17") (pin "1") (pinfunction "1_1") (pintype "passive"))
      (node (ref "R20") (pin "1") (pinfunction "1_1") (pintype "passive"))
      (node (ref "R21") (pin "2") (pinfunction "2_2") (pintype "passive"))
      (node (ref "U4") (pin "1") (pinfunction "INA_1") (pintype "passive"))
    )
    (net (code "41") (name "Net-(U4-INB)") (class "Default")
      (node (ref "C16") (pin "1") (pinfunction "1_1") (pintype "passive"))
      (node (ref "R19") (pin "1") (pinfunction "1_1") (pintype "passive"))
      (node (ref "R22") (pin "2") (pinfunction "2_2") (pintype "passive"))
      (node (ref "U4") (pin "2") (pinfunction "INB_2") (pintype "passive"))
    )
    (net (code "42") (name "Net-(U4-OUTA)") (class "Default")
      (node (ref "D2") (pin "C") (pinfunction "C_C") (pintype "passive"))
      (node (ref "R17") (pin "1") (pinfunction "1_1") (pintype "passive"))
      (node (ref "U4") (pin "15") (pinfunction "OUTA_15") (pintype "passive"))
    )
    (net (code "43") (name "Net-(U4-OUTB)") (class "Default")
      (node (ref "D3") (pin "C") (pinfunction "C_C") (pintype "passive"))
      (node (ref "R25") (pin "2") (pinfunction "2_2") (pintype "passive"))
      (node (ref "U4") (pin "10") (pinfunction "OUTB_10") (pintype "passive"))
    )
    (net (code "44") (name "Net-(U5-DISABLE)") (class "Default")
      (node (ref "C25") (pin "1") (pinfunction "1_1") (pintype "passive"))
      (node (ref "R30") (pin "1") (pinfunction "1_1") (pintype "passive"))
      (node (ref "R35") (pin "2") (pinfunction "2_2") (pintype "passive"))
      (node (ref "U5") (pin "5") (pinfunction "DISABLE_5") (pintype "passive"))
    )
    (net (code "45") (name "Net-(U5-DT)") (class "Default")
      (node (ref "C28") (pin "2") (pinfunction "2_2") (pintype "passive"))
      (node (ref "R36") (pin "2") (pinfunction "2_2") (pintype "passive"))
      (node (ref "U5") (pin "6") (pinfunction "DT_6") (pintype "passive"))
    )
    (net (code "46") (name "Net-(U5-INA)") (class "Default")
      (node (ref "C27") (pin "1") (pinfunction "1_1") (pintype "passive"))
      (node (ref "R32") (pin "1") (pinfunction "1_1") (pintype "passive"))
      (node (ref "R33") (pin "2") (pinfunction "2_2") (pintype "passive"))
      (node (ref "U5") (pin "1") (pinfunction "INA_1") (pintype "passive"))
    )
    (net (code "47") (name "Net-(U5-INB)") (class "Default")
      (node (ref "C26") (pin "1") (pinfunction "1_1") (pintype "passive"))
      (node (ref "R31") (pin "1") (pinfunction "1_1") (pintype "passive"))
      (node (ref "R34") (pin "2") (pinfunction "2_2") (pintype "passive"))
      (node (ref "U5") (pin "2") (pinfunction "INB_2") (pintype "passive"))
    )
    (net (code "48") (name "Net-(U5-OUTA)") (class "Default")
      (node (ref "D5") (pin "C") (pinfunction "C_C") (pintype "passive"))
      (node (ref "R29") (pin "1") (pinfunction "1_1") (pintype "passive"))
      (node (ref "U5") (pin "15") (pinfunction "OUTA_15") (pintype "passive"))
    )
    (net (code "49") (name "Net-(U5-OUTB)") (class "Default")
      (node (ref "D6") (pin "C") (pinfunction "C_C") (pintype "passive"))
      (node (ref "R37") (pin "2") (pinfunction "2_2") (pintype "passive"))
      (node (ref "U5") (pin "10") (pinfunction "OUTB_10") (pintype "passive"))
    )
    (net (code "50") (name "Net-(U6-DISABLE)") (class "Default")
      (node (ref "C35") (pin "1") (pinfunction "1_1") (pintype "passive"))
      (node (ref "R42") (pin "1") (pinfunction "1_1") (pintype "passive"))
      (node (ref "R47") (pin "2") (pinfunction "2_2") (pintype "passive"))
      (node (ref "U6") (pin "5") (pinfunction "DISABLE_5") (pintype "passive"))
    )
    (net (code "51") (name "Net-(U6-DT)") (class "Default")
      (node (ref "C38") (pin "2") (pinfunction "2_2") (pintype "passive"))
      (node (ref "R48") (pin "2") (pinfunction "2_2") (pintype "passive"))
      (node (ref "U6") (pin "6") (pinfunction "DT_6") (pintype "passive"))
    )
    (net (code "52") (name "Net-(U6-INA)") (class "Default")
      (node (ref "C37") (pin "1") (pinfunction "1_1") (pintype "passive"))
      (node (ref "R44") (pin "1") (pinfunction "1_1") (pintype "passive"))
      (node (ref "R45") (pin "2") (pinfunction "2_2") (pintype "passive"))
      (node (ref "U6") (pin "1") (pinfunction "INA_1") (pintype "passive"))
    )
    (net (code "53") (name "Net-(U6-INB)") (class "Default")
      (node (ref "C36") (pin "1") (pinfunction "1_1") (pintype "passive"))
      (node (ref "R43") (pin "1") (pinfunction "1_1") (pintype "passive"))
      (node (ref "R46") (pin "2") (pinfunction "2_2") (pintype "passive"))
      (node (ref "U6") (pin "2") (pinfunction "INB_2") (pintype "passive"))
    )
    (net (code "54") (name "Net-(U6-OUTA)") (class "Default")
      (node (ref "D8") (pin "C") (pinfunction "C_C") (pintype "passive"))
      (node (ref "R41") (pin "1") (pinfunction "1_1") (pintype "passive"))
      (node (ref "U6") (pin "15") (pinfunction "OUTA_15") (pintype "passive"))
    )
    (net (code "55") (name "Net-(U6-OUTB)") (class "Default")
      (node (ref "D9") (pin "C") (pinfunction "C_C") (pintype "passive"))
      (node (ref "R49") (pin "2") (pinfunction "2_2") (pintype "passive"))
      (node (ref "U6") (pin "10") (pinfunction "OUTB_10") (pintype "passive"))
    )
    (net (code "56") (name "VIN+") (class "Default")
      (node (ref "J24") (pin "1") (pinfunction "1_1") (pintype "passive"))
      (node (ref "J24") (pin "2") (pinfunction "2_2") (pintype "passive"))
      (node (ref "J24") (pin "3") (pinfunction "3_3") (pintype "passive"))
      (node (ref "J24") (pin "4") (pinfunction "4_4") (pintype "passive"))
      (node (ref "J24") (pin "5") (pinfunction "5_5") (pintype "passive"))
      (node (ref "J24") (pin "6") (pinfunction "6_6") (pintype "passive"))
    )
    (net (code "57") (name "unconnected-(U4-NC_1-Pad7)") (class "Default")
      (node (ref "U4") (pin "7") (pinfunction "NC_1_7") (pintype "passive"))
    )
    (net (code "58") (name "unconnected-(U4-NC_2-Pad12)") (class "Default")
      (node (ref "U4") (pin "12") (pinfunction "NC_2_12") (pintype "passive"))
    )
    (net (code "59") (name "unconnected-(U4-NC_3-Pad13)") (class "Default")
      (node (ref "U4") (pin "13") (pinfunction "NC_3_13") (pintype "passive"))
    )
    (net (code "60") (name "unconnected-(U5-NC_1-Pad7)") (class "Default")
      (node (ref "U5") (pin "7") (pinfunction "NC_1_7") (pintype "passive"))
    )
    (net (code "61") (name "unconnected-(U5-NC_2-Pad12)") (class "Default")
      (node (ref "U5") (pin "12") (pinfunction "NC_2_12") (pintype "passive"))
    )
    (net (code "62") (name "unconnected-(U5-NC_3-Pad13)") (class "Default")
      (node (ref "U5") (pin "13") (pinfunction "NC_3_13") (pintype "passive"))
    )
    (net (code "63") (name "unconnected-(U6-NC_1-Pad7)") (class "Default")
      (node (ref "U6") (pin "7") (pinfunction "NC_1_7") (pintype "passive"))
    )
    (net (code "64") (name "unconnected-(U6-NC_2-Pad12)") (class "Default")
      (node (ref "U6") (pin "12") (pinfunction "NC_2_12") (pintype "passive"))
    )
    (net (code "65") (name "unconnected-(U6-NC_3-Pad13)") (class "Default")
      (node (ref "U6") (pin "13") (pinfunction "NC_3_13") (pintype "passive"))
    )
  )
)
